# E3-Thermal_Sensor_v2.net
KiCad netlist of a schematic drawn in EAGLE
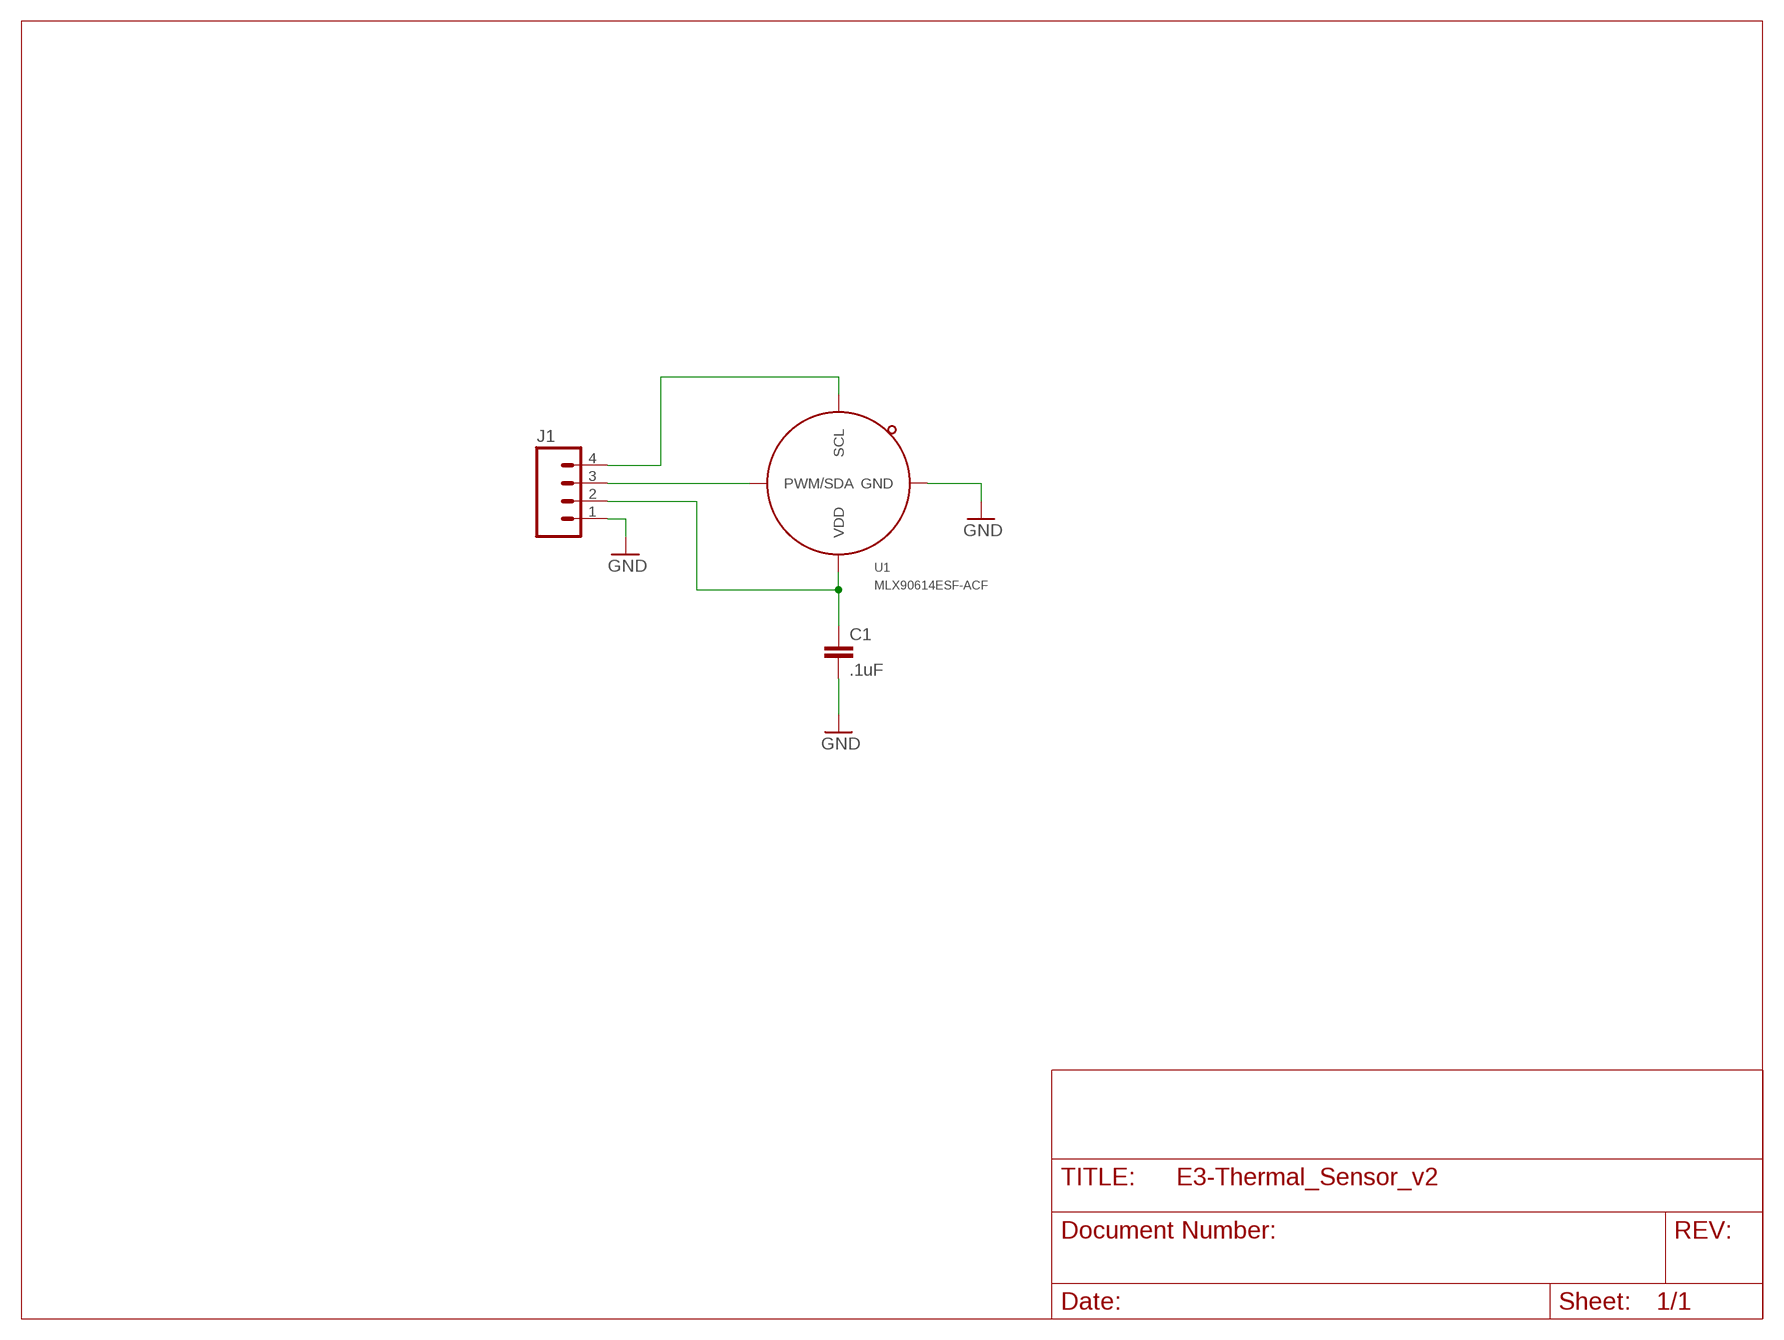
[diagram p0: schematic, sheet 1]

(export (version "E")
  (design (tool "Eeschema 10.0.6"))
  (components
    (comp (ref "C1")
      (value ".1uF")
      (footprint "eagle-import:0603-CAP")
      (libsource (lib "eagle-import") (part "CAP0603-CAP"))
    )
    (comp (ref "J1")
      (value "M04PTH")
      (footprint "eagle-import:1X04")
      (libsource (lib "eagle-import") (part "M04PTH"))
    )
    (comp (ref "U1")
      (value "MLX90614ESF-ACF")
      (footprint "eagle-import:MLX90614XCF")
      (libsource (lib "eagle-import") (part "MLX90614ESF-ACF"))
    )
  )
  (nets
    (net (code "1") (name "GND") (class "Default")
      (node (ref "C1") (pin "2") (pinfunction "2_2") (pintype "passive"))
      (node (ref "J1") (pin "1") (pinfunction "1_1") (pintype "passive"))
      (node (ref "U1") (pin "P4") (pinfunction "GND_P4") (pintype "bidirectional"))
    )
    (net (code "2") (name "Net-(U1-PWM{slash}SDA)") (class "Default")
      (node (ref "J1") (pin "3") (pinfunction "3_3") (pintype "passive"))
      (node (ref "U1") (pin "P2") (pinfunction "PWM/SDA_P2") (pintype "bidirectional"))
    )
    (net (code "3") (name "Net-(U1-SCL)") (class "Default")
      (node (ref "J1") (pin "4") (pinfunction "4_4") (pintype "passive"))
      (node (ref "U1") (pin "P1") (pinfunction "SCL_P1") (pintype "bidirectional"))
    )
    (net (code "4") (name "Net-(U1-VDD)") (class "Default")
      (node (ref "C1") (pin "1") (pinfunction "1_1") (pintype "passive"))
      (node (ref "J1") (pin "2") (pinfunction "2_2") (pintype "passive"))
      (node (ref "U1") (pin "P3") (pinfunction "VDD_P3") (pintype "bidirectional"))
    )
  )
)
